# charger.net
KiCad netlist of a schematic drawn in Altium Designer
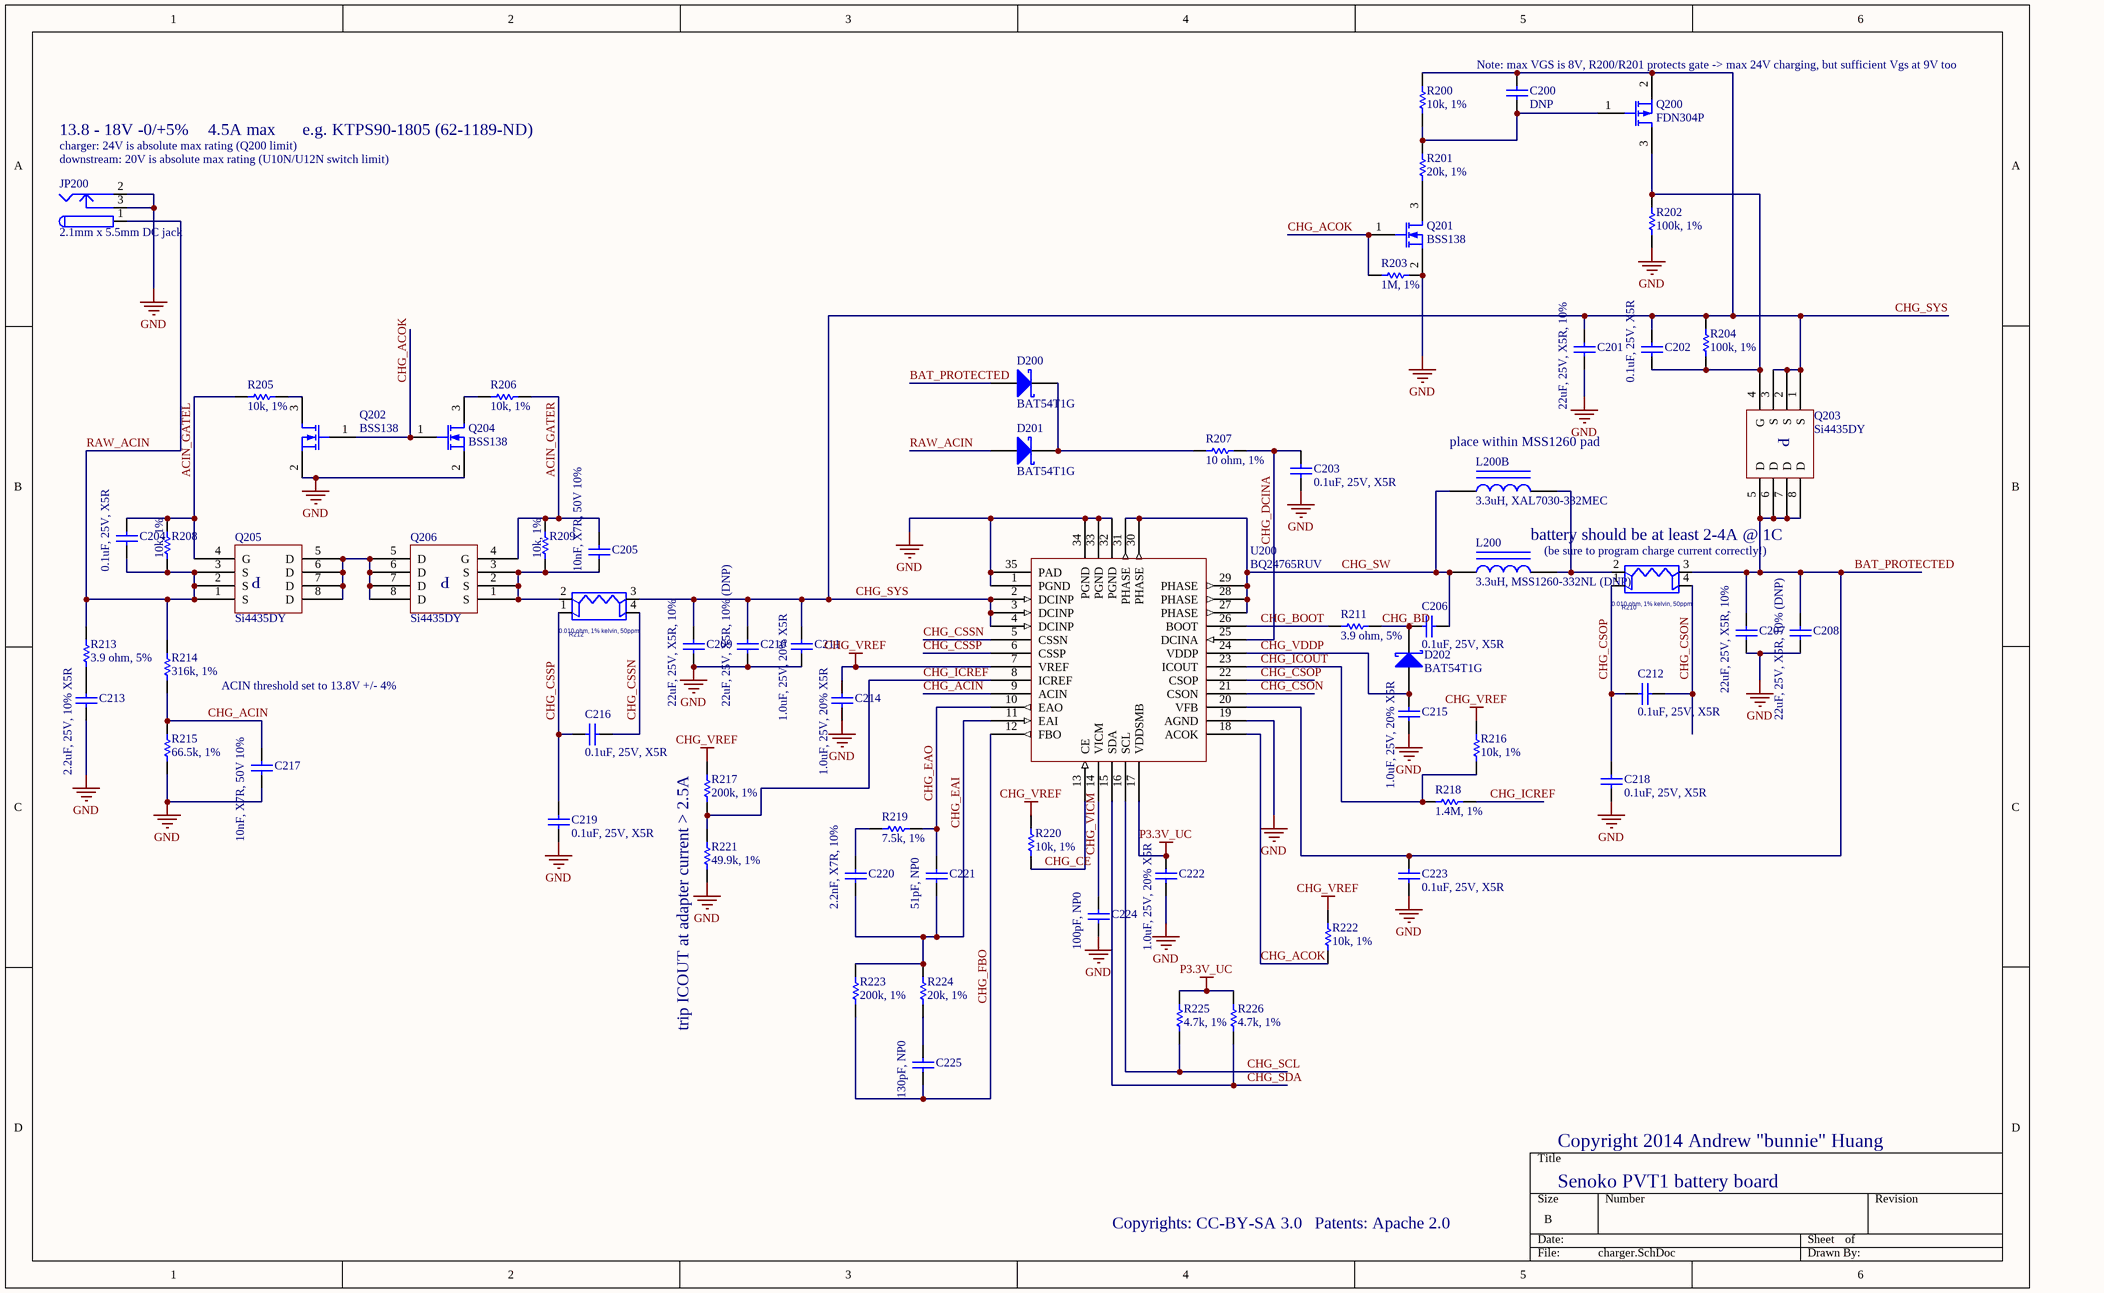
[diagram p0: charger.SchDoc]

(export (version "E")
  (design (tool "Eeschema 10.0.6"))
  (components
    (comp (ref "C200")
      (value "DNP")
      (footprint "CAPC1005N")
      (description "Capacitor (Semiconductor SIM Model)")
      (fields (field (name "PUBLISHER") "Altium Limited"))
      (libsource (lib "Miscellaneous Devices") (part "Cap Semi"))
    )
    (comp (ref "C201")
      (value "22uF, 25V, X5R, 10%")
      (footprint "CAPC3225N")
      (description "Capacitor (Semiconductor SIM Model)")
      (fields (field (name "PUBLISHER") "Altium Limited"))
      (libsource (lib "Miscellaneous Devices") (part "Cap Semi"))
    )
    (comp (ref "C202")
      (value "0.1uF, 25V, X5R")
      (footprint "CAPC1005N")
      (description "Capacitor (Semiconductor SIM Model)")
      (fields (field (name "PUBLISHER") "Altium Limited"))
      (libsource (lib "Miscellaneous Devices") (part "Cap Semi"))
    )
    (comp (ref "C203")
      (value "0.1uF, 25V, X5R")
      (footprint "CAPC1005N")
      (description "Capacitor (Semiconductor SIM Model)")
      (fields (field (name "PUBLISHER") "Altium Limited"))
      (libsource (lib "Miscellaneous Devices") (part "Cap Semi"))
    )
    (comp (ref "C204")
      (value "0.1uF, 25V, X5R")
      (footprint "CAPC1005N")
      (description "Capacitor (Semiconductor SIM Model)")
      (fields (field (name "PUBLISHER") "Altium Limited"))
      (libsource (lib "Miscellaneous Devices") (part "Cap Semi"))
    )
    (comp (ref "C205")
      (value "10nF, X7R, 50V 10%")
      (footprint "CAPC1005N")
      (description "Capacitor (Semiconductor SIM Model)")
      (fields (field (name "PUBLISHER") "Altium Limited"))
      (libsource (lib "Miscellaneous Devices") (part "Cap Semi"))
    )
    (comp (ref "C206")
      (value "0.1uF, 25V, X5R")
      (footprint "CAPC1005N")
      (description "Capacitor (Semiconductor SIM Model)")
      (fields (field (name "PUBLISHER") "Altium Limited"))
      (libsource (lib "Miscellaneous Devices") (part "Cap Semi"))
    )
    (comp (ref "C207")
      (value "22uF, 25V, X5R, 10%")
      (footprint "CAPC3225N")
      (description "Capacitor (Semiconductor SIM Model)")
      (fields (field (name "PUBLISHER") "Altium Limited"))
      (libsource (lib "Miscellaneous Devices") (part "Cap Semi"))
    )
    (comp (ref "C208")
      (value "22uF, 25V, X5R, 10% (DNP)")
      (footprint "CAPC3225N")
      (description "Capacitor (Semiconductor SIM Model)")
      (fields (field (name "PUBLISHER") "Altium Limited"))
      (libsource (lib "Miscellaneous Devices") (part "Cap Semi"))
    )
    (comp (ref "C209")
      (value "22uF, 25V, X5R, 10%")
      (footprint "CAPC3225N")
      (description "Capacitor (Semiconductor SIM Model)")
      (fields (field (name "PUBLISHER") "Altium Limited"))
      (libsource (lib "Miscellaneous Devices") (part "Cap Semi"))
    )
    (comp (ref "C210")
      (value "22uF, 25V, X5R, 10% (DNP)")
      (footprint "CAPC3225N")
      (description "Capacitor (Semiconductor SIM Model)")
      (fields (field (name "PUBLISHER") "Altium Limited"))
      (libsource (lib "Miscellaneous Devices") (part "Cap Semi"))
    )
    (comp (ref "C211")
      (value "1.0uF, 25V, 20% X5R")
      (footprint "CAPC1608N")
      (description "Capacitor (Semiconductor SIM Model)")
      (fields (field (name "PUBLISHER") "Altium Limited"))
      (libsource (lib "Miscellaneous Devices") (part "Cap Semi"))
    )
    (comp (ref "C212")
      (value "0.1uF, 25V, X5R")
      (footprint "CAPC1005N")
      (description "Capacitor (Semiconductor SIM Model)")
      (fields (field (name "PUBLISHER") "Altium Limited"))
      (libsource (lib "Miscellaneous Devices") (part "Cap Semi"))
    )
    (comp (ref "C213")
      (value "2.2uF, 25V, 10% X5R")
      (footprint "CAPC1608N")
      (description "Capacitor (Semiconductor SIM Model)")
      (fields (field (name "PUBLISHER") "Altium Limited"))
      (libsource (lib "Miscellaneous Devices") (part "Cap Semi"))
    )
    (comp (ref "C214")
      (value "1.0uF, 25V, 20% X5R")
      (footprint "CAPC1608N")
      (description "Capacitor (Semiconductor SIM Model)")
      (fields (field (name "PUBLISHER") "Altium Limited"))
      (libsource (lib "Miscellaneous Devices") (part "Cap Semi"))
    )
    (comp (ref "C215")
      (value "1.0uF, 25V, 20% X5R")
      (footprint "CAPC1608N")
      (description "Capacitor (Semiconductor SIM Model)")
      (fields (field (name "PUBLISHER") "Altium Limited"))
      (libsource (lib "Miscellaneous Devices") (part "Cap Semi"))
    )
    (comp (ref "C216")
      (value "0.1uF, 25V, X5R")
      (footprint "CAPC1005N")
      (description "Capacitor (Semiconductor SIM Model)")
      (fields (field (name "PUBLISHER") "Altium Limited"))
      (libsource (lib "Miscellaneous Devices") (part "Cap Semi"))
    )
    (comp (ref "C217")
      (value "10nF, X7R, 50V 10%")
      (footprint "CAPC1005N")
      (description "Capacitor (Semiconductor SIM Model)")
      (fields (field (name "PUBLISHER") "Altium Limited"))
      (libsource (lib "Miscellaneous Devices") (part "Cap Semi"))
    )
    (comp (ref "C218")
      (value "0.1uF, 25V, X5R")
      (footprint "CAPC1005N")
      (description "Capacitor (Semiconductor SIM Model)")
      (fields (field (name "PUBLISHER") "Altium Limited"))
      (libsource (lib "Miscellaneous Devices") (part "Cap Semi"))
    )
    (comp (ref "C219")
      (value "0.1uF, 25V, X5R")
      (footprint "CAPC1005N")
      (description "Capacitor (Semiconductor SIM Model)")
      (fields (field (name "PUBLISHER") "Altium Limited"))
      (libsource (lib "Miscellaneous Devices") (part "Cap Semi"))
    )
    (comp (ref "C220")
      (value "2.2nF, X7R, 10%")
      (footprint "CAPC1005N")
      (description "Capacitor (Semiconductor SIM Model)")
      (fields (field (name "PUBLISHER") "Altium Limited"))
      (libsource (lib "Miscellaneous Devices") (part "Cap Semi"))
    )
    (comp (ref "C221")
      (value "51pF, NP0")
      (footprint "CAPC1005N")
      (description "Capacitor (Semiconductor SIM Model)")
      (fields (field (name "PUBLISHER") "Altium Limited"))
      (libsource (lib "Miscellaneous Devices") (part "Cap Semi"))
    )
    (comp (ref "C222")
      (value "1.0uF, 25V, 20% X5R")
      (footprint "CAPC1608N")
      (description "Capacitor (Semiconductor SIM Model)")
      (fields (field (name "PUBLISHER") "Altium Limited"))
      (libsource (lib "Miscellaneous Devices") (part "Cap Semi"))
    )
    (comp (ref "C223")
      (value "0.1uF, 25V, X5R")
      (footprint "CAPC1005N")
      (description "Capacitor (Semiconductor SIM Model)")
      (fields (field (name "PUBLISHER") "Altium Limited"))
      (libsource (lib "Miscellaneous Devices") (part "Cap Semi"))
    )
    (comp (ref "C224")
      (value "100pF, NP0")
      (footprint "CAPC1005N")
      (description "Capacitor (Semiconductor SIM Model)")
      (fields (field (name "PUBLISHER") "Altium Limited"))
      (libsource (lib "Miscellaneous Devices") (part "Cap Semi"))
    )
    (comp (ref "C225")
      (value "130pF, NP0")
      (footprint "CAPC1005N")
      (description "Capacitor (Semiconductor SIM Model)")
      (fields (field (name "PUBLISHER") "Altium Limited"))
      (libsource (lib "Miscellaneous Devices") (part "Cap Semi"))
    )
    (comp (ref "D200")
      (value "BAT54T1G")
      (footprint "SOD123")
      (description "Schottky Diode")
      (fields (field (name "PUBLISHER") "Altium Limited"))
      (libsource (lib "Miscellaneous Devices") (part "D Schottky"))
    )
    (comp (ref "D201")
      (value "BAT54T1G")
      (footprint "SOD123")
      (description "Schottky Diode")
      (fields (field (name "PUBLISHER") "Altium Limited"))
      (libsource (lib "Miscellaneous Devices") (part "D Schottky"))
    )
    (comp (ref "D202")
      (value "BAT54T1G")
      (footprint "SOD123")
      (description "Schottky Diode")
      (fields (field (name "PUBLISHER") "Altium Limited"))
      (libsource (lib "Miscellaneous Devices") (part "D Schottky"))
    )
    (comp (ref "JP200")
      (value "2.1mm x 5.5mm DC jack")
      (footprint "CUI_PJ_002AH_SMT")
      (description "Low Voltage Power Supply Connector")
      (fields (field (name "PUBLISHER") "Altium Limited"))
      (libsource (lib "Miscellaneous Connectors") (part "PWR2.5"))
    )
    (comp (ref "L200")
      (value "3.3uH, MSS1260-332NL (DNP)")
      (footprint "COILCRAFT_MSS1048")
      (description "Magnetic-Core Inductor")
      (fields (field (name "PUBLISHER") "Altium Limited"))
      (libsource (lib "Miscellaneous Devices") (part "Inductor Iron"))
    )
    (comp (ref "L200B")
      (value "3.3uH, XAL7030-332MEC")
      (footprint "COILCRAFT_XAL7030")
      (description "Magnetic-Core Inductor")
      (fields (field (name "PUBLISHER") "Altium Limited"))
      (libsource (lib "Miscellaneous Devices") (part "Inductor Iron"))
    )
    (comp (ref "Q200")
      (value "FDN304P")
      (footprint "SOT23-3N")
      (description "P-Channel MOSFET")
      (fields (field (name "PUBLISHER") "Altium Limited"))
      (libsource (lib "Miscellaneous Devices") (part "MOSFET-P"))
    )
    (comp (ref "Q201")
      (value "BSS138")
      (footprint "SOT23-3N")
      (description "N-Channel MOSFET")
      (fields (field (name "PUBLISHER") "Altium Limited"))
      (libsource (lib "Miscellaneous Devices") (part "MOSFET-N"))
    )
    (comp (ref "Q202")
      (value "BSS138")
      (footprint "SOT23-3N")
      (description "N-Channel MOSFET")
      (fields (field (name "PUBLISHER") "Altium Limited"))
      (libsource (lib "Miscellaneous Devices") (part "MOSFET-N"))
    )
    (comp (ref "Q203")
      (value "Si4435DY")
      (footprint "SOIC127P600-8AN")
      (description "Singre P-channel FET, 8A, 30V")
      (libsource (lib "") (part "Si4435DY_2"))
    )
    (comp (ref "Q204")
      (value "BSS138")
      (footprint "SOT23-3N")
      (description "N-Channel MOSFET")
      (fields (field (name "PUBLISHER") "Altium Limited"))
      (libsource (lib "Miscellaneous Devices") (part "MOSFET-N"))
    )
    (comp (ref "Q205")
      (value "Si4435DY")
      (footprint "SOIC127P600-8AN")
      (description "Singre P-channel FET, 8A, 30V")
      (libsource (lib "") (part "Si4435DY_1"))
    )
    (comp (ref "Q206")
      (value "Si4435DY")
      (footprint "SOIC127P600-8AN")
      (description "Singre P-channel FET, 8A, 30V")
      (libsource (lib "commonsch") (part "Si4435DY"))
    )
    (comp (ref "R200")
      (value "10k, 1%")
      (footprint "RESC1005N")
      (description "Resistor")
      (fields (field (name "PUBLISHER") "Altium Limited"))
      (libsource (lib "Miscellaneous Devices") (part "Res1"))
    )
    (comp (ref "R201")
      (value "20k, 1%")
      (footprint "RESC1005N")
      (description "Resistor")
      (fields (field (name "PUBLISHER") "Altium Limited"))
      (libsource (lib "Miscellaneous Devices") (part "Res1"))
    )
    (comp (ref "R202")
      (value "100k, 1%")
      (footprint "RESC1005N")
      (description "Resistor")
      (fields (field (name "PUBLISHER") "Altium Limited"))
      (libsource (lib "Miscellaneous Devices") (part "Res1"))
    )
    (comp (ref "R203")
      (value "1M, 1%")
      (footprint "RESC1005N")
      (description "Resistor")
      (fields (field (name "PUBLISHER") "Altium Limited"))
      (libsource (lib "Miscellaneous Devices") (part "Res1"))
    )
    (comp (ref "R204")
      (value "100k, 1%")
      (footprint "RESC1005N")
      (description "Resistor")
      (fields (field (name "PUBLISHER") "Altium Limited"))
      (libsource (lib "Miscellaneous Devices") (part "Res1"))
    )
    (comp (ref "R205")
      (value "10k, 1%")
      (footprint "RESC1005N")
      (description "Resistor")
      (fields (field (name "PUBLISHER") "Altium Limited"))
      (libsource (lib "Miscellaneous Devices") (part "Res1"))
    )
    (comp (ref "R206")
      (value "10k, 1%")
      (footprint "RESC1005N")
      (description "Resistor")
      (fields (field (name "PUBLISHER") "Altium Limited"))
      (libsource (lib "Miscellaneous Devices") (part "Res1"))
    )
    (comp (ref "R207")
      (value "10 ohm, 1%")
      (footprint "RESC1005N")
      (description "Resistor")
      (fields (field (name "PUBLISHER") "Altium Limited"))
      (libsource (lib "Miscellaneous Devices") (part "Res1"))
    )
    (comp (ref "R208")
      (value "10k, 1%")
      (footprint "RESC1005N")
      (description "Resistor")
      (fields (field (name "PUBLISHER") "Altium Limited"))
      (libsource (lib "Miscellaneous Devices") (part "Res1"))
    )
    (comp (ref "R209")
      (value "10k, 1%")
      (footprint "RESC1005N")
      (description "Resistor")
      (fields (field (name "PUBLISHER") "Altium Limited"))
      (libsource (lib "Miscellaneous Devices") (part "Res1"))
    )
    (comp (ref "R210")
      (value "0.010 ohm, 1% kelvin, 50ppm")
      (fields
        (field (name "PART_NUMBER") "R00034-001")
        (field (name "TOLERANCE") "?")
        (field (name "MFG") "OHMITE")
      )
      (libsource (lib "*") (part "RES_4TERM"))
    )
    (comp (ref "R211")
      (value "3.9 ohm, 5%")
      (footprint "RESC1005N")
      (description "Resistor")
      (fields (field (name "PUBLISHER") "Altium Limited"))
      (libsource (lib "Miscellaneous Devices") (part "Res1"))
    )
    (comp (ref "R212")
      (value "0.010 ohm, 1% kelvin, 50ppm")
      (fields
        (field (name "PART_NUMBER") "R00034-001")
        (field (name "TOLERANCE") "?")
        (field (name "MFG") "OHMITE")
      )
      (libsource (lib "*") (part "RES_4TERM"))
    )
    (comp (ref "R213")
      (value "3.9 ohm, 5%")
      (footprint "RESC1005N")
      (description "Resistor")
      (fields (field (name "PUBLISHER") "Altium Limited"))
      (libsource (lib "Miscellaneous Devices") (part "Res1"))
    )
    (comp (ref "R214")
      (value "316k, 1%")
      (footprint "RESC1005N")
      (description "Resistor")
      (fields (field (name "PUBLISHER") "Altium Limited"))
      (libsource (lib "Miscellaneous Devices") (part "Res1"))
    )
    (comp (ref "R215")
      (value "66.5k, 1%")
      (footprint "RESC1005N")
      (description "Resistor")
      (fields (field (name "PUBLISHER") "Altium Limited"))
      (libsource (lib "Miscellaneous Devices") (part "Res1"))
    )
    (comp (ref "R216")
      (value "10k, 1%")
      (footprint "RESC1005N")
      (description "Resistor")
      (fields (field (name "PUBLISHER") "Altium Limited"))
      (libsource (lib "Miscellaneous Devices") (part "Res1"))
    )
    (comp (ref "R217")
      (value "200k, 1%")
      (footprint "RESC1005N")
      (description "Resistor")
      (fields (field (name "PUBLISHER") "Altium Limited"))
      (libsource (lib "Miscellaneous Devices") (part "Res1"))
    )
    (comp (ref "R218")
      (value "1.4M, 1%")
      (footprint "RESC1005N")
      (description "Resistor")
      (fields (field (name "PUBLISHER") "Altium Limited"))
      (libsource (lib "Miscellaneous Devices") (part "Res1"))
    )
    (comp (ref "R219")
      (value "7.5k, 1%")
      (footprint "RESC1005N")
      (description "Resistor")
      (fields (field (name "PUBLISHER") "Altium Limited"))
      (libsource (lib "Miscellaneous Devices") (part "Res1"))
    )
    (comp (ref "R220")
      (value "10k, 1%")
      (footprint "RESC1005N")
      (description "Resistor")
      (fields (field (name "PUBLISHER") "Altium Limited"))
      (libsource (lib "Miscellaneous Devices") (part "Res1"))
    )
    (comp (ref "R221")
      (value "49.9k, 1%")
      (footprint "RESC1005N")
      (description "Resistor")
      (fields (field (name "PUBLISHER") "Altium Limited"))
      (libsource (lib "Miscellaneous Devices") (part "Res1"))
    )
    (comp (ref "R222")
      (value "10k, 1%")
      (footprint "RESC1005N")
      (description "Resistor")
      (fields (field (name "PUBLISHER") "Altium Limited"))
      (libsource (lib "Miscellaneous Devices") (part "Res1"))
    )
    (comp (ref "R223")
      (value "200k, 1%")
      (footprint "RESC1005N")
      (description "Resistor")
      (fields (field (name "PUBLISHER") "Altium Limited"))
      (libsource (lib "Miscellaneous Devices") (part "Res1"))
    )
    (comp (ref "R224")
      (value "20k, 1%")
      (footprint "RESC1005N")
      (description "Resistor")
      (fields (field (name "PUBLISHER") "Altium Limited"))
      (libsource (lib "Miscellaneous Devices") (part "Res1"))
    )
    (comp (ref "R225")
      (value "4.7k, 1%")
      (footprint "RESC1005N")
      (description "Resistor")
      (fields (field (name "PUBLISHER") "Altium Limited"))
      (libsource (lib "Miscellaneous Devices") (part "Res1"))
    )
    (comp (ref "R226")
      (value "4.7k, 1%")
      (footprint "RESC1005N")
      (description "Resistor")
      (fields (field (name "PUBLISHER") "Altium Limited"))
      (libsource (lib "Miscellaneous Devices") (part "Res1"))
    )
    (comp (ref "U200")
      (value "BQ24765RUV")
      (footprint "TI_R-PVQFN-N34")
      (description "SMBus-controlled battery charger with integrated FETs")
      (libsource (lib "commonsch") (part "BQ24765RUV"))
    )
  )
  (nets
    (net (code "1") (name "/ACIN_GATEL") (class "Default")
      (node (ref "C204") (pin "1") (pinfunction "1_1") (pintype "passive"))
      (node (ref "Q205") (pin "4") (pinfunction "G_4") (pintype "passive"))
      (node (ref "R205") (pin "1") (pinfunction "1_1") (pintype "passive"))
      (node (ref "R208") (pin "2") (pinfunction "2_2") (pintype "passive"))
    )
    (net (code "2") (name "/ACIN_GATER") (class "Default")
      (node (ref "C205") (pin "1") (pinfunction "1_1") (pintype "passive"))
      (node (ref "Q206") (pin "4") (pinfunction "G_4") (pintype "passive"))
      (node (ref "R206") (pin "2") (pinfunction "2_2") (pintype "passive"))
      (node (ref "R209") (pin "2") (pinfunction "2_2") (pintype "passive"))
    )
    (net (code "3") (name "/BAT_PROTECTED") (class "Default")
      (node (ref "C207") (pin "1") (pinfunction "1_1") (pintype "passive"))
      (node (ref "C208") (pin "1") (pinfunction "1_1") (pintype "passive"))
      (node (ref "C223") (pin "2") (pinfunction "2_2") (pintype "passive"))
      (node (ref "D200") (pin "1") (pinfunction "A_1") (pintype "passive"))
      (node (ref "Q203") (pin "5") (pinfunction "D_5") (pintype "passive"))
      (node (ref "Q203") (pin "6") (pinfunction "D_6") (pintype "passive"))
      (node (ref "Q203") (pin "7") (pinfunction "D_7") (pintype "passive"))
      (node (ref "Q203") (pin "8") (pinfunction "D_8") (pintype "passive"))
      (node (ref "R210") (pin "3") (pinfunction "3_3") (pintype "bidirectional"))
      (node (ref "U200") (pin "20") (pinfunction "VFB_20") (pintype "passive"))
    )
    (net (code "4") (name "/CHG_ACIN") (class "Default")
      (node (ref "C217") (pin "1") (pinfunction "1_1") (pintype "passive"))
      (node (ref "R214") (pin "2") (pinfunction "2_2") (pintype "passive"))
      (node (ref "R215") (pin "1") (pinfunction "1_1") (pintype "passive"))
      (node (ref "U200") (pin "9") (pinfunction "ACIN_9") (pintype "passive"))
    )
    (net (code "5") (name "/CHG_ACOK") (class "Default")
      (node (ref "Q201") (pin "1") (pinfunction "G_1") (pintype "passive"))
      (node (ref "Q202") (pin "1") (pinfunction "G_1") (pintype "passive"))
      (node (ref "Q204") (pin "1") (pinfunction "G_1") (pintype "passive"))
      (node (ref "R203") (pin "2") (pinfunction "2_2") (pintype "passive"))
      (node (ref "R222") (pin "2") (pinfunction "2_2") (pintype "passive"))
      (node (ref "U200") (pin "18") (pinfunction "ACOK_18") (pintype "open_collector"))
    )
    (net (code "6") (name "/CHG_BD") (class "Default")
      (node (ref "C206") (pin "1") (pinfunction "1_1") (pintype "passive"))
      (node (ref "D202") (pin "2") (pinfunction "K_2") (pintype "passive"))
      (node (ref "R211") (pin "2") (pinfunction "2_2") (pintype "passive"))
    )
    (net (code "7") (name "/CHG_BOOT") (class "Default")
      (node (ref "R211") (pin "1") (pinfunction "1_1") (pintype "passive"))
      (node (ref "U200") (pin "26") (pinfunction "BOOT_26") (pintype "passive"))
    )
    (net (code "8") (name "/CHG_CE") (class "Default")
      (node (ref "R220") (pin "2") (pinfunction "2_2") (pintype "passive"))
      (node (ref "U200") (pin "13") (pinfunction "CE_13") (pintype "input"))
    )
    (net (code "9") (name "/CHG_CSON") (class "Default")
      (node (ref "C212") (pin "1") (pinfunction "1_1") (pintype "passive"))
      (node (ref "R210") (pin "4") (pinfunction "4_4") (pintype "bidirectional"))
      (node (ref "U200") (pin "21") (pinfunction "CSON_21") (pintype "passive"))
    )
    (net (code "10") (name "/CHG_CSOP") (class "Default")
      (node (ref "C212") (pin "2") (pinfunction "2_2") (pintype "passive"))
      (node (ref "C218") (pin "2") (pinfunction "2_2") (pintype "passive"))
      (node (ref "R210") (pin "1") (pinfunction "1_1") (pintype "bidirectional"))
      (node (ref "U200") (pin "22") (pinfunction "CSOP_22") (pintype "passive"))
    )
    (net (code "11") (name "/CHG_CSSN") (class "Default")
      (node (ref "C216") (pin "2") (pinfunction "2_2") (pintype "passive"))
      (node (ref "R212") (pin "4") (pinfunction "4_4") (pintype "bidirectional"))
      (node (ref "U200") (pin "5") (pinfunction "CSSN_5") (pintype "passive"))
    )
    (net (code "12") (name "/CHG_CSSP") (class "Default")
      (node (ref "C216") (pin "1") (pinfunction "1_1") (pintype "passive"))
      (node (ref "C219") (pin "1") (pinfunction "1_1") (pintype "passive"))
      (node (ref "R212") (pin "1") (pinfunction "1_1") (pintype "bidirectional"))
      (node (ref "U200") (pin "6") (pinfunction "CSSP_6") (pintype "passive"))
    )
    (net (code "13") (name "/CHG_DCINA") (class "Default")
      (node (ref "C203") (pin "1") (pinfunction "1_1") (pintype "passive"))
      (node (ref "R207") (pin "2") (pinfunction "2_2") (pintype "passive"))
      (node (ref "U200") (pin "25") (pinfunction "DCINA_25") (pintype "input"))
    )
    (net (code "14") (name "/CHG_EAI") (class "Default")
      (node (ref "C220") (pin "2") (pinfunction "2_2") (pintype "passive"))
      (node (ref "C221") (pin "2") (pinfunction "2_2") (pintype "passive"))
      (node (ref "R223") (pin "1") (pinfunction "1_1") (pintype "passive"))
      (node (ref "R224") (pin "1") (pinfunction "1_1") (pintype "passive"))
      (node (ref "U200") (pin "11") (pinfunction "EAI_11") (pintype "input"))
    )
    (net (code "15") (name "/CHG_EAO") (class "Default")
      (node (ref "C221") (pin "1") (pinfunction "1_1") (pintype "passive"))
      (node (ref "R219") (pin "2") (pinfunction "2_2") (pintype "passive"))
      (node (ref "U200") (pin "10") (pinfunction "EAO_10") (pintype "output"))
    )
    (net (code "16") (name "/CHG_FBO") (class "Default")
      (node (ref "C225") (pin "2") (pinfunction "2_2") (pintype "passive"))
      (node (ref "R223") (pin "2") (pinfunction "2_2") (pintype "passive"))
      (node (ref "U200") (pin "12") (pinfunction "FBO_12") (pintype "output"))
    )
    (net (code "17") (name "/CHG_ICOUT") (class "Default")
      (node (ref "R216") (pin "2") (pinfunction "2_2") (pintype "passive"))
      (node (ref "R218") (pin "2") (pinfunction "2_2") (pintype "passive"))
      (node (ref "U200") (pin "23") (pinfunction "ICOUT_23") (pintype "open_collector"))
    )
    (net (code "18") (name "/CHG_ICREF") (class "Default")
      (node (ref "R217") (pin "2") (pinfunction "2_2") (pintype "passive"))
      (node (ref "R218") (pin "1") (pinfunction "1_1") (pintype "passive"))
      (node (ref "R221") (pin "1") (pinfunction "1_1") (pintype "passive"))
      (node (ref "U200") (pin "8") (pinfunction "ICREF_8") (pintype "passive"))
    )
    (net (code "19") (name "/CHG_SCL") (class "Default")
      (node (ref "R225") (pin "2") (pinfunction "2_2") (pintype "passive"))
      (node (ref "U200") (pin "16") (pinfunction "SCL_16") (pintype "open_emitter"))
    )
    (net (code "20") (name "/CHG_SDA") (class "Default")
      (node (ref "R226") (pin "2") (pinfunction "2_2") (pintype "passive"))
      (node (ref "U200") (pin "15") (pinfunction "SDA_15") (pintype "open_emitter"))
    )
    (net (code "21") (name "/CHG_SW") (class "Default")
      (node (ref "C206") (pin "2") (pinfunction "2_2") (pintype "passive"))
      (node (ref "L200") (pin "1") (pinfunction "1_1") (pintype "passive"))
      (node (ref "L200B") (pin "1") (pinfunction "1_1") (pintype "passive"))
      (node (ref "U200") (pin "27") (pinfunction "PHASE_27") (pintype "output"))
      (node (ref "U200") (pin "28") (pinfunction "PHASE_28") (pintype "output"))
      (node (ref "U200") (pin "29") (pinfunction "PHASE_29") (pintype "output"))
      (node (ref "U200") (pin "30") (pinfunction "PHASE_30") (pintype "output"))
      (node (ref "U200") (pin "31") (pinfunction "PHASE_31") (pintype "output"))
    )
    (net (code "22") (name "/CHG_SYS") (class "Default")
      (node (ref "C200") (pin "2") (pinfunction "2_2") (pintype "passive"))
      (node (ref "C201") (pin "1") (pinfunction "1_1") (pintype "passive"))
      (node (ref "C202") (pin "1") (pinfunction "1_1") (pintype "passive"))
      (node (ref "C209") (pin "1") (pinfunction "1_1") (pintype "passive"))
      (node (ref "C210") (pin "1") (pinfunction "1_1") (pintype "passive"))
      (node (ref "C211") (pin "1") (pinfunction "1_1") (pintype "passive"))
      (node (ref "Q200") (pin "2") (pinfunction "S_2") (pintype "passive"))
      (node (ref "Q203") (pin "1") (pinfunction "S_1") (pintype "passive"))
      (node (ref "Q203") (pin "2") (pinfunction "S_2") (pintype "passive"))
      (node (ref "Q203") (pin "3") (pinfunction "S_3") (pintype "passive"))
      (node (ref "R200") (pin "1") (pinfunction "1_1") (pintype "passive"))
      (node (ref "R204") (pin "1") (pinfunction "1_1") (pintype "passive"))
      (node (ref "R212") (pin "3") (pinfunction "3_3") (pintype "bidirectional"))
      (node (ref "U200") (pin "2") (pinfunction "DCINP_2") (pintype "input"))
      (node (ref "U200") (pin "3") (pinfunction "DCINP_3") (pintype "input"))
      (node (ref "U200") (pin "4") (pinfunction "DCINP_4") (pintype "input"))
    )
    (net (code "23") (name "/CHG_VDDP") (class "Default")
      (node (ref "C215") (pin "1") (pinfunction "1_1") (pintype "passive"))
      (node (ref "D202") (pin "1") (pinfunction "A_1") (pintype "passive"))
      (node (ref "U200") (pin "24") (pinfunction "VDDP_24") (pintype "power_in"))
    )
    (net (code "24") (name "/CHG_VICM") (class "Default")
      (node (ref "C224") (pin "1") (pinfunction "1_1") (pintype "passive"))
      (node (ref "U200") (pin "14") (pinfunction "VICM_14") (pintype "passive"))
    )
    (net (code "25") (name "/RAW_ACIN") (class "Default")
      (node (ref "C204") (pin "2") (pinfunction "2_2") (pintype "passive"))
      (node (ref "D201") (pin "1") (pinfunction "A_1") (pintype "passive"))
      (node (ref "JP200") (pin "1") (pintype "power_in"))
      (node (ref "Q205") (pin "1") (pinfunction "S_1") (pintype "passive"))
      (node (ref "Q205") (pin "2") (pinfunction "S_2") (pintype "passive"))
      (node (ref "Q205") (pin "3") (pinfunction "S_3") (pintype "passive"))
      (node (ref "R208") (pin "1") (pinfunction "1_1") (pintype "passive"))
      (node (ref "R213") (pin "1") (pinfunction "1_1") (pintype "passive"))
      (node (ref "R214") (pin "1") (pinfunction "1_1") (pintype "passive"))
    )
    (net (code "26") (name "CHG_VREF") (class "Default")
      (node (ref "C214") (pin "1") (pinfunction "1_1") (pintype "passive"))
      (node (ref "R216") (pin "1") (pinfunction "1_1") (pintype "passive"))
      (node (ref "R217") (pin "1") (pinfunction "1_1") (pintype "passive"))
      (node (ref "R220") (pin "1") (pinfunction "1_1") (pintype "passive"))
      (node (ref "R222") (pin "1") (pinfunction "1_1") (pintype "passive"))
      (node (ref "U200") (pin "7") (pinfunction "VREF_7") (pintype "power_in"))
    )
    (net (code "27") (name "GND") (class "Default")
      (node (ref "C201") (pin "2") (pinfunction "2_2") (pintype "passive"))
      (node (ref "C203") (pin "2") (pinfunction "2_2") (pintype "passive"))
      (node (ref "C207") (pin "2") (pinfunction "2_2") (pintype "passive"))
      (node (ref "C208") (pin "2") (pinfunction "2_2") (pintype "passive"))
      (node (ref "C209") (pin "2") (pinfunction "2_2") (pintype "passive"))
      (node (ref "C210") (pin "2") (pinfunction "2_2") (pintype "passive"))
      (node (ref "C211") (pin "2") (pinfunction "2_2") (pintype "passive"))
      (node (ref "C213") (pin "2") (pinfunction "2_2") (pintype "passive"))
      (node (ref "C214") (pin "2") (pinfunction "2_2") (pintype "passive"))
      (node (ref "C215") (pin "2") (pinfunction "2_2") (pintype "passive"))
      (node (ref "C217") (pin "2") (pinfunction "2_2") (pintype "passive"))
      (node (ref "C218") (pin "1") (pinfunction "1_1") (pintype "passive"))
      (node (ref "C219") (pin "2") (pinfunction "2_2") (pintype "passive"))
      (node (ref "C222") (pin "2") (pinfunction "2_2") (pintype "passive"))
      (node (ref "C223") (pin "1") (pinfunction "1_1") (pintype "passive"))
      (node (ref "C224") (pin "2") (pinfunction "2_2") (pintype "passive"))
      (node (ref "JP200") (pin "2") (pintype "power_in"))
      (node (ref "JP200") (pin "3") (pintype "power_in"))
      (node (ref "Q201") (pin "2") (pinfunction "S_2") (pintype "passive"))
      (node (ref "Q202") (pin "2") (pinfunction "S_2") (pintype "passive"))
      (node (ref "Q204") (pin "2") (pinfunction "S_2") (pintype "passive"))
      (node (ref "R202") (pin "2") (pinfunction "2_2") (pintype "passive"))
      (node (ref "R203") (pin "1") (pinfunction "1_1") (pintype "passive"))
      (node (ref "R215") (pin "2") (pinfunction "2_2") (pintype "passive"))
      (node (ref "R221") (pin "2") (pinfunction "2_2") (pintype "passive"))
      (node (ref "U200") (pin "1") (pinfunction "PGND_1") (pintype "power_in"))
      (node (ref "U200") (pin "19") (pinfunction "AGND_19") (pintype "power_in"))
      (node (ref "U200") (pin "32") (pinfunction "PGND_32") (pintype "power_in"))
      (node (ref "U200") (pin "33") (pinfunction "PGND_33") (pintype "power_in"))
      (node (ref "U200") (pin "34") (pinfunction "PGND_34") (pintype "power_in"))
      (node (ref "U200") (pin "35") (pinfunction "PAD_35") (pintype "power_in"))
    )
    (net (code "28") (name "Net-(C205-Pad2)") (class "Default")
      (node (ref "C205") (pin "2") (pinfunction "2_2") (pintype "passive"))
      (node (ref "Q206") (pin "1") (pinfunction "S_1") (pintype "passive"))
      (node (ref "Q206") (pin "2") (pinfunction "S_2") (pintype "passive"))
      (node (ref "Q206") (pin "3") (pinfunction "S_3") (pintype "passive"))
      (node (ref "R209") (pin "1") (pinfunction "1_1") (pintype "passive"))
      (node (ref "R212") (pin "2") (pinfunction "2_2") (pintype "bidirectional"))
    )
    (net (code "29") (name "Net-(C213-Pad1)") (class "Default")
      (node (ref "C213") (pin "1") (pinfunction "1_1") (pintype "passive"))
      (node (ref "R213") (pin "2") (pinfunction "2_2") (pintype "passive"))
    )
    (net (code "30") (name "Net-(C220-Pad1)") (class "Default")
      (node (ref "C220") (pin "1") (pinfunction "1_1") (pintype "passive"))
      (node (ref "R219") (pin "1") (pinfunction "1_1") (pintype "passive"))
    )
    (net (code "31") (name "Net-(C225-Pad1)") (class "Default")
      (node (ref "C225") (pin "1") (pinfunction "1_1") (pintype "passive"))
      (node (ref "R224") (pin "2") (pinfunction "2_2") (pintype "passive"))
    )
    (net (code "32") (name "Net-(D200-K)") (class "Default")
      (node (ref "D200") (pin "2") (pinfunction "K_2") (pintype "passive"))
      (node (ref "D201") (pin "2") (pinfunction "K_2") (pintype "passive"))
      (node (ref "R207") (pin "1") (pinfunction "1_1") (pintype "passive"))
    )
    (net (code "33") (name "Net-(L200-Pad2)") (class "Default")
      (node (ref "L200") (pin "2") (pinfunction "2_2") (pintype "passive"))
      (node (ref "L200B") (pin "2") (pinfunction "2_2") (pintype "passive"))
      (node (ref "R210") (pin "2") (pinfunction "2_2") (pintype "bidirectional"))
    )
    (net (code "34") (name "Net-(Q200-D)") (class "Default")
      (node (ref "C202") (pin "2") (pinfunction "2_2") (pintype "passive"))
      (node (ref "Q200") (pin "3") (pinfunction "D_3") (pintype "passive"))
      (node (ref "Q203") (pin "4") (pinfunction "G_4") (pintype "passive"))
      (node (ref "R202") (pin "1") (pinfunction "1_1") (pintype "passive"))
      (node (ref "R204") (pin "2") (pinfunction "2_2") (pintype "passive"))
    )
    (net (code "35") (name "Net-(Q200-G)") (class "Default")
      (node (ref "C200") (pin "1") (pinfunction "1_1") (pintype "passive"))
      (node (ref "Q200") (pin "1") (pinfunction "G_1") (pintype "passive"))
      (node (ref "R200") (pin "2") (pinfunction "2_2") (pintype "passive"))
      (node (ref "R201") (pin "1") (pinfunction "1_1") (pintype "passive"))
    )
    (net (code "36") (name "Net-(Q201-D)") (class "Default")
      (node (ref "Q201") (pin "3") (pinfunction "D_3") (pintype "passive"))
      (node (ref "R201") (pin "2") (pinfunction "2_2") (pintype "passive"))
    )
    (net (code "37") (name "Net-(Q202-D)") (class "Default")
      (node (ref "Q202") (pin "3") (pinfunction "D_3") (pintype "passive"))
      (node (ref "R205") (pin "2") (pinfunction "2_2") (pintype "passive"))
    )
    (net (code "38") (name "Net-(Q204-D)") (class "Default")
      (node (ref "Q204") (pin "3") (pinfunction "D_3") (pintype "passive"))
      (node (ref "R206") (pin "1") (pinfunction "1_1") (pintype "passive"))
    )
    (net (code "39") (name "Net-(Q205-D-Pad5)") (class "Default")
      (node (ref "Q205") (pin "5") (pinfunction "D_5") (pintype "passive"))
      (node (ref "Q205") (pin "6") (pinfunction "D_6") (pintype "passive"))
      (node (ref "Q205") (pin "7") (pinfunction "D_7") (pintype "passive"))
      (node (ref "Q205") (pin "8") (pinfunction "D_8") (pintype "passive"))
      (node (ref "Q206") (pin "5") (pinfunction "D_5") (pintype "passive"))
      (node (ref "Q206") (pin "6") (pinfunction "D_6") (pintype "passive"))
      (node (ref "Q206") (pin "7") (pinfunction "D_7") (pintype "passive"))
      (node (ref "Q206") (pin "8") (pinfunction "D_8") (pintype "passive"))
    )
    (net (code "40") (name "P3.3V_UC") (class "Default")
      (node (ref "C222") (pin "1") (pinfunction "1_1") (pintype "passive"))
      (node (ref "R225") (pin "1") (pinfunction "1_1") (pintype "passive"))
      (node (ref "R226") (pin "1") (pinfunction "1_1") (pintype "passive"))
      (node (ref "U200") (pin "17") (pinfunction "VDDSMB_17") (pintype "power_in"))
    )
  )
)
